# Sheet4.net
KiCad netlist of a schematic drawn in Altium Designer
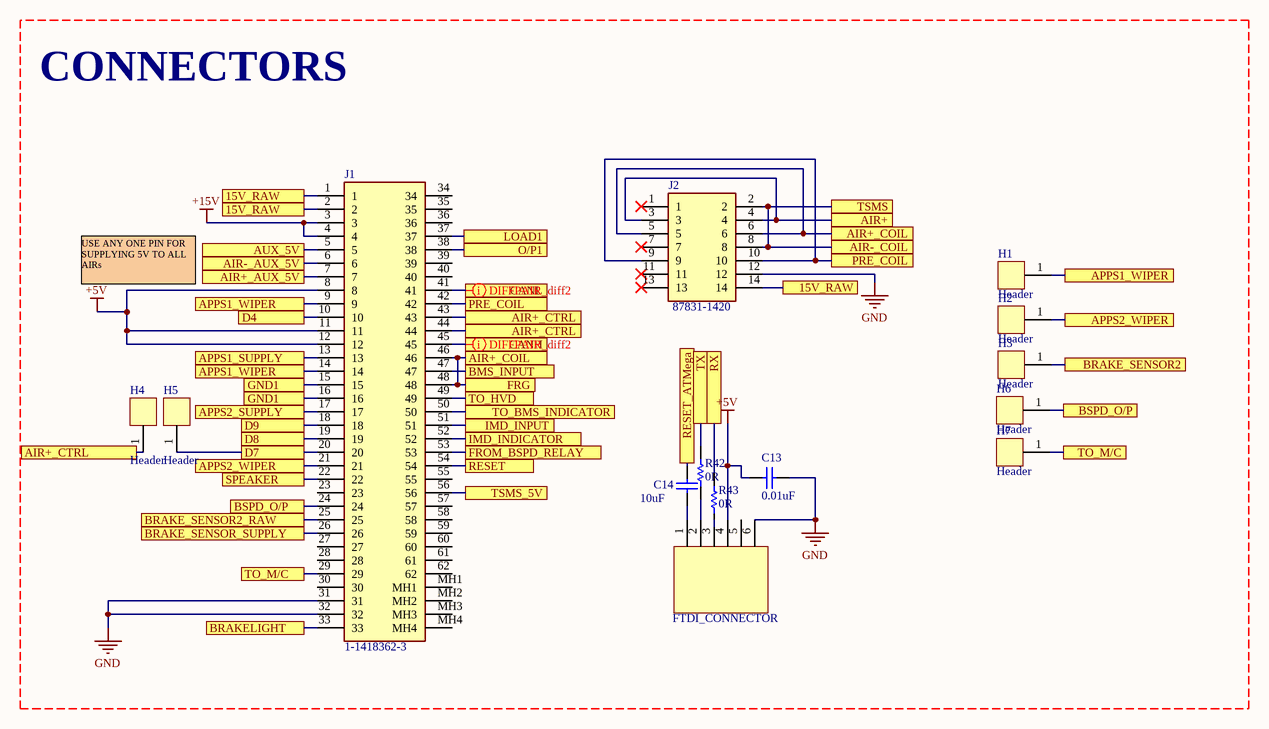
[diagram p0: Sheet4.SchDoc]

(export (version "E")
  (design (tool "Eeschema 10.0.6"))
  (components
    (comp (ref "2")
      (value "FTDI_connector")
      (footprint "ARDUINO_MEGA_NO_SILK")
      (libsource (lib "Schlib1") (part "FTDI_connector"))
    )
    (comp (ref "C13")
      (value "0.01uF")
      (footprint "KEMT-1206-2_N")
      (description "CAP, Ceramic, 0.1 uF, +/- 10%, 50 V, -55 to 125 degC, 1206 (3216 Metric), RoHS, Tape and Reel")
      (fields (field (name "MANUFACTURER") "Kemet"))
      (libsource (lib "Schlib1_TSAL_LV_3.1") (part "CMP-1037-04202-2"))
    )
    (comp (ref "C14")
      (value "10uF")
      (footprint "KEMT-1206-2_N")
      (description "CAP, Ceramic, 0.1 uF, +/- 10%, 50 V, -55 to 125 degC, 1206 (3216 Metric), RoHS, Tape and Reel")
      (fields (field (name "MANUFACTURER") "Kemet"))
      (libsource (lib "Schlib1_TSAL_LV_3.1") (part "CMP-1037-04202-2"))
    )
    (comp (ref "H1") (value "Header") (footprint "Header") (libsource (lib "") (part "Header_1")))
    (comp (ref "H2") (value "Header") (footprint "Header") (libsource (lib "") (part "Header_1")))
    (comp (ref "H3") (value "Header") (footprint "Header") (libsource (lib "") (part "Header_1")))
    (comp (ref "H4") (value "Header") (footprint "Header") (libsource (lib "Schlib1") (part "Header")))
    (comp (ref "H5") (value "Header") (footprint "Header") (libsource (lib "Schlib1") (part "Header")))
    (comp (ref "H6") (value "Header") (footprint "Header") (libsource (lib "") (part "Header_1")))
    (comp (ref "H7") (value "Header") (footprint "Header") (libsource (lib "") (part "Header_1")))
    (comp (ref "J1")
      (value "1-1418362-3")
      (footprint "SamacSys:114183623")
      (description "Connector")
      (fields (field (name "MOUSER PART NUMBER") "571-1-1418362-3"))
      (libsource (lib "SamacSys") (part "1-1418362-3"))
    )
    (comp (ref "J2")
      (value "87831-1420")
      (footprint "SamacSys:SHDR14W55P200_2X7_1665X630X640P")
      (description "Connector")
      (fields (field (name "MOUSER PART NUMBER") "538-87831-1420"))
      (libsource (lib "SamacSys") (part "87831-1420"))
    )
    (comp (ref "R42")
      (value "0R")
      (footprint "R1206")
      (fields (field (name "PART NUMBER") "CRCW120647K0FKEA") (field (name "MANUFACTURER") "Vishay Dale"))
      (libsource (lib "Schlib1") (part "RES"))
    )
    (comp (ref "R43")
      (value "0R")
      (footprint "R1206")
      (fields (field (name "PART NUMBER") "CRCW120647K0FKEA") (field (name "MANUFACTURER") "Vishay Dale"))
      (libsource (lib "Schlib1") (part "RES"))
    )
  )
  (nets
    (net (code "1") (name "+5V") (class "Default")
      (node (ref "2") (pin "4") (pinfunction "4_4") (pintype "passive"))
      (node (ref "C13") (pin "2") (pinfunction "2_2") (pintype "passive"))
      (node (ref "J1") (pin "11") (pinfunction "11_11") (pintype "passive"))
      (node (ref "J1") (pin "12") (pinfunction "12_12") (pintype "passive"))
      (node (ref "J1") (pin "8") (pinfunction "8_8") (pintype "passive"))
    )
    (net (code "2") (name "+15V") (class "Default")
      (node (ref "J1") (pin "3") (pinfunction "3_3") (pintype "passive"))
      (node (ref "J1") (pin "4") (pinfunction "4_4") (pintype "passive"))
    )
    (net (code "3") (name "/15V_RAW") (class "Default")
      (node (ref "J1") (pin "1") (pinfunction "1_1") (pintype "passive"))
      (node (ref "J1") (pin "2") (pinfunction "2_2") (pintype "passive"))
      (node (ref "J2") (pin "14") (pinfunction "14_14") (pintype "passive"))
    )
    (net (code "4") (name "/AIR+") (class "Default")
      (node (ref "J2") (pin "3") (pinfunction "3_3") (pintype "passive"))
      (node (ref "J2") (pin "4") (pinfunction "4_4") (pintype "passive"))
    )
    (net (code "5") (name "/AIR+_AUX_5V") (class "Default")
      (node (ref "J1") (pin "7") (pinfunction "7_7") (pintype "passive"))
    )
    (net (code "6") (name "/AIR+_COIL") (class "Default")
      (node (ref "J1") (pin "46") (pinfunction "46_46") (pintype "passive"))
      (node (ref "J1") (pin "48") (pinfunction "48_48") (pintype "passive"))
      (node (ref "J2") (pin "5") (pinfunction "5_5") (pintype "passive"))
      (node (ref "J2") (pin "6") (pinfunction "6_6") (pintype "passive"))
    )
    (net (code "7") (name "/AIR+_CTRL") (class "Default")
      (node (ref "H4") (pin "1") (pinfunction "1_1") (pintype "passive"))
      (node (ref "J1") (pin "43") (pinfunction "43_43") (pintype "passive"))
      (node (ref "J1") (pin "44") (pinfunction "44_44") (pintype "passive"))
    )
    (net (code "8") (name "/AIR-_AUX_5V") (class "Default")
      (node (ref "J1") (pin "6") (pinfunction "6_6") (pintype "passive"))
    )
    (net (code "9") (name "/AIR-_COIL") (class "Default")
      (node (ref "J2") (pin "2") (pinfunction "2_2") (pintype "passive"))
      (node (ref "J2") (pin "8") (pinfunction "8_8") (pintype "passive"))
    )
    (net (code "10") (name "/APPS1_SUPPLY") (class "Default")
      (node (ref "J1") (pin "13") (pinfunction "13_13") (pintype "passive"))
    )
    (net (code "11") (name "/APPS1_WIPER") (class "Default")
      (node (ref "H1") (pin "1") (pinfunction "1_1") (pintype "passive"))
      (node (ref "J1") (pin "14") (pinfunction "14_14") (pintype "passive"))
      (node (ref "J1") (pin "9") (pinfunction "9_9") (pintype "passive"))
    )
    (net (code "12") (name "/APPS2_SUPPLY") (class "Default")
      (node (ref "J1") (pin "17") (pinfunction "17_17") (pintype "passive"))
    )
    (net (code "13") (name "/APPS2_WIPER") (class "Default")
      (node (ref "H2") (pin "1") (pinfunction "1_1") (pintype "passive"))
      (node (ref "J1") (pin "21") (pinfunction "21_21") (pintype "passive"))
    )
    (net (code "14") (name "/AUX_5V") (class "Default")
      (node (ref "J1") (pin "5") (pinfunction "5_5") (pintype "passive"))
    )
    (net (code "15") (name "/BMS_INPUT") (class "Default")
      (node (ref "J1") (pin "47") (pinfunction "47_47") (pintype "passive"))
    )
    (net (code "16") (name "/BRAKELIGHT") (class "Default")
      (node (ref "J1") (pin "33") (pinfunction "33_33") (pintype "passive"))
    )
    (net (code "17") (name "/BRAKE_SENSOR2") (class "Default")
      (node (ref "H3") (pin "1") (pinfunction "1_1") (pintype "passive"))
    )
    (net (code "18") (name "/BRAKE_SENSOR2_RAW") (class "Default")
      (node (ref "J1") (pin "25") (pinfunction "25_25") (pintype "passive"))
    )
    (net (code "19") (name "/BRAKE_SENSOR_SUPPLY") (class "Default")
      (node (ref "J1") (pin "26") (pinfunction "26_26") (pintype "passive"))
    )
    (net (code "20") (name "/BSPD_O{slash}P") (class "Default")
      (node (ref "H6") (pin "1") (pinfunction "1_1") (pintype "passive"))
      (node (ref "J1") (pin "24") (pinfunction "24_24") (pintype "passive"))
    )
    (net (code "21") (name "/CANH") (class "Default")
      (node (ref "J1") (pin "45") (pinfunction "45_45") (pintype "passive"))
    )
    (net (code "22") (name "/CANL") (class "Default")
      (node (ref "J1") (pin "41") (pinfunction "41_41") (pintype "passive"))
    )
    (net (code "23") (name "/D4") (class "Default")
      (node (ref "J1") (pin "10") (pinfunction "10_10") (pintype "passive"))
    )
    (net (code "24") (name "/D7") (class "Default")
      (node (ref "H5") (pin "1") (pinfunction "1_1") (pintype "passive"))
      (node (ref "J1") (pin "20") (pinfunction "20_20") (pintype "passive"))
    )
    (net (code "25") (name "/D8") (class "Default")
      (node (ref "J1") (pin "19") (pinfunction "19_19") (pintype "passive"))
    )
    (net (code "26") (name "/D9") (class "Default")
      (node (ref "J1") (pin "18") (pinfunction "18_18") (pintype "passive"))
    )
    (net (code "27") (name "/FROM_BSPD_RELAY") (class "Default")
      (node (ref "J1") (pin "53") (pinfunction "53_53") (pintype "passive"))
    )
    (net (code "28") (name "/GND1") (class "Default")
      (node (ref "J1") (pin "15") (pinfunction "15_15") (pintype "passive"))
      (node (ref "J1") (pin "16") (pinfunction "16_16") (pintype "passive"))
    )
    (net (code "29") (name "/IMD_INDICATOR") (class "Default")
      (node (ref "J1") (pin "52") (pinfunction "52_52") (pintype "passive"))
    )
    (net (code "30") (name "/IMD_INPUT") (class "Default")
      (node (ref "J1") (pin "51") (pinfunction "51_51") (pintype "passive"))
    )
    (net (code "31") (name "/LOAD1") (class "Default")
      (node (ref "J1") (pin "37") (pinfunction "37_37") (pintype "passive"))
    )
    (net (code "32") (name "/O{slash}P1") (class "Default")
      (node (ref "J1") (pin "38") (pinfunction "38_38") (pintype "passive"))
    )
    (net (code "33") (name "/PRE_COIL") (class "Default")
      (node (ref "J1") (pin "42") (pinfunction "42_42") (pintype "passive"))
      (node (ref "J2") (pin "10") (pinfunction "10_10") (pintype "passive"))
      (node (ref "J2") (pin "9") (pinfunction "9_9") (pintype "passive"))
    )
    (net (code "34") (name "/RESET") (class "Default")
      (node (ref "J1") (pin "54") (pinfunction "54_54") (pintype "passive"))
    )
    (net (code "35") (name "/RESET_ATMega") (class "Default")
      (node (ref "C14") (pin "2") (pinfunction "2_2") (pintype "passive"))
    )
    (net (code "36") (name "/RX") (class "Default")
      (node (ref "R43") (pin "1") (pinfunction "1_1") (pintype "passive"))
    )
    (net (code "37") (name "/SPEAKER") (class "Default")
      (node (ref "J1") (pin "22") (pinfunction "22_22") (pintype "passive"))
    )
    (net (code "38") (name "/TO_BMS_INDICATOR") (class "Default")
      (node (ref "J1") (pin "50") (pinfunction "50_50") (pintype "passive"))
    )
    (net (code "39") (name "/TO_HVD") (class "Default")
      (node (ref "J1") (pin "49") (pinfunction "49_49") (pintype "passive"))
    )
    (net (code "40") (name "/TO_M{slash}C") (class "Default")
      (node (ref "H7") (pin "1") (pinfunction "1_1") (pintype "passive"))
      (node (ref "J1") (pin "29") (pinfunction "29_29") (pintype "passive"))
    )
    (net (code "41") (name "/TSMS_5V") (class "Default")
      (node (ref "J1") (pin "56") (pinfunction "56_56") (pintype "passive"))
    )
    (net (code "42") (name "/TX") (class "Default")
      (node (ref "R42") (pin "1") (pinfunction "1_1") (pintype "passive"))
    )
    (net (code "43") (name "GND") (class "Default")
      (node (ref "2") (pin "6") (pinfunction "6_6") (pintype "passive"))
      (node (ref "C13") (pin "1") (pinfunction "1_1") (pintype "passive"))
      (node (ref "J1") (pin "31") (pinfunction "31_31") (pintype "passive"))
      (node (ref "J1") (pin "32") (pinfunction "32_32") (pintype "passive"))
      (node (ref "J2") (pin "12") (pinfunction "12_12") (pintype "passive"))
    )
    (net (code "44") (name "Net-(2-4-Pad3)") (class "Default")
      (node (ref "2") (pin "3") (pinfunction "4_3") (pintype "passive"))
      (node (ref "R43") (pin "2") (pinfunction "2_2") (pintype "passive"))
    )
    (net (code "45") (name "Net-(2-Pad1)") (class "Default")
      (node (ref "2") (pin "1") (pinfunction "1_1") (pintype "passive"))
      (node (ref "C14") (pin "1") (pinfunction "1_1") (pintype "passive"))
    )
    (net (code "46") (name "Net-(2-Pad2)") (class "Default")
      (node (ref "2") (pin "2") (pinfunction "2_2") (pintype "passive"))
      (node (ref "R42") (pin "2") (pinfunction "2_2") (pintype "passive"))
    )
    (net (code "47") (name "unconnected-(2-2-Pad5)") (class "Default")
      (node (ref "2") (pin "5") (pinfunction "2_5") (pintype "passive"))
    )
    (net (code "48") (name "unconnected-(J1-Pad23)") (class "Default")
      (node (ref "J1") (pin "23") (pinfunction "23_23") (pintype "passive"))
    )
    (net (code "49") (name "unconnected-(J1-Pad27)") (class "Default")
      (node (ref "J1") (pin "27") (pinfunction "27_27") (pintype "passive"))
    )
    (net (code "50") (name "unconnected-(J1-Pad28)") (class "Default")
      (node (ref "J1") (pin "28") (pinfunction "28_28") (pintype "passive"))
    )
    (net (code "51") (name "unconnected-(J1-Pad30)") (class "Default")
      (node (ref "J1") (pin "30") (pinfunction "30_30") (pintype "passive"))
    )
    (net (code "52") (name "unconnected-(J1-Pad34)") (class "Default")
      (node (ref "J1") (pin "34") (pinfunction "34_34") (pintype "passive"))
    )
    (net (code "53") (name "unconnected-(J1-Pad35)") (class "Default")
      (node (ref "J1") (pin "35") (pinfunction "35_35") (pintype "passive"))
    )
    (net (code "54") (name "unconnected-(J1-Pad36)") (class "Default")
      (node (ref "J1") (pin "36") (pinfunction "36_36") (pintype "passive"))
    )
    (net (code "55") (name "unconnected-(J1-Pad39)") (class "Default")
      (node (ref "J1") (pin "39") (pinfunction "39_39") (pintype "passive"))
    )
    (net (code "56") (name "unconnected-(J1-Pad40)") (class "Default")
      (node (ref "J1") (pin "40") (pinfunction "40_40") (pintype "passive"))
    )
    (net (code "57") (name "unconnected-(J1-Pad55)") (class "Default")
      (node (ref "J1") (pin "55") (pinfunction "55_55") (pintype "passive"))
    )
    (net (code "58") (name "unconnected-(J1-Pad57)") (class "Default")
      (node (ref "J1") (pin "57") (pinfunction "57_57") (pintype "passive"))
    )
    (net (code "59") (name "unconnected-(J1-Pad58)") (class "Default")
      (node (ref "J1") (pin "58") (pinfunction "58_58") (pintype "passive"))
    )
    (net (code "60") (name "unconnected-(J1-Pad59)") (class "Default")
      (node (ref "J1") (pin "59") (pinfunction "59_59") (pintype "passive"))
    )
    (net (code "61") (name "unconnected-(J1-Pad60)") (class "Default")
      (node (ref "J1") (pin "60") (pinfunction "60_60") (pintype "passive"))
    )
    (net (code "62") (name "unconnected-(J1-Pad61)") (class "Default")
      (node (ref "J1") (pin "61") (pinfunction "61_61") (pintype "passive"))
    )
    (net (code "63") (name "unconnected-(J1-Pad62)") (class "Default")
      (node (ref "J1") (pin "62") (pinfunction "62_62") (pintype "passive"))
    )
    (net (code "64") (name "unconnected-(J1-PadMH1)") (class "Default")
      (node (ref "J1") (pin "MH1") (pinfunction "MH1_MH1") (pintype "passive"))
    )
    (net (code "65") (name "unconnected-(J1-PadMH2)") (class "Default")
      (node (ref "J1") (pin "MH2") (pinfunction "MH2_MH2") (pintype "passive"))
    )
    (net (code "66") (name "unconnected-(J1-PadMH3)") (class "Default")
      (node (ref "J1") (pin "MH3") (pinfunction "MH3_MH3") (pintype "passive"))
    )
    (net (code "67") (name "unconnected-(J1-PadMH4)") (class "Default")
      (node (ref "J1") (pin "MH4") (pinfunction "MH4_MH4") (pintype "passive"))
    )
    (net (code "68") (name "unconnected-(J2-Pad1)") (class "Default")
      (node (ref "J2") (pin "1") (pinfunction "1_1") (pintype "passive+no_connect"))
    )
    (net (code "69") (name "unconnected-(J2-Pad7)") (class "Default")
      (node (ref "J2") (pin "7") (pinfunction "7_7") (pintype "passive+no_connect"))
    )
    (net (code "70") (name "unconnected-(J2-Pad11)") (class "Default")
      (node (ref "J2") (pin "11") (pinfunction "11_11") (pintype "passive+no_connect"))
    )
    (net (code "71") (name "unconnected-(J2-Pad13)") (class "Default")
      (node (ref "J2") (pin "13") (pinfunction "13_13") (pintype "passive+no_connect"))
    )
  )
)
